# cell_adapter.net
KiCad netlist of a schematic drawn in Altium Designer
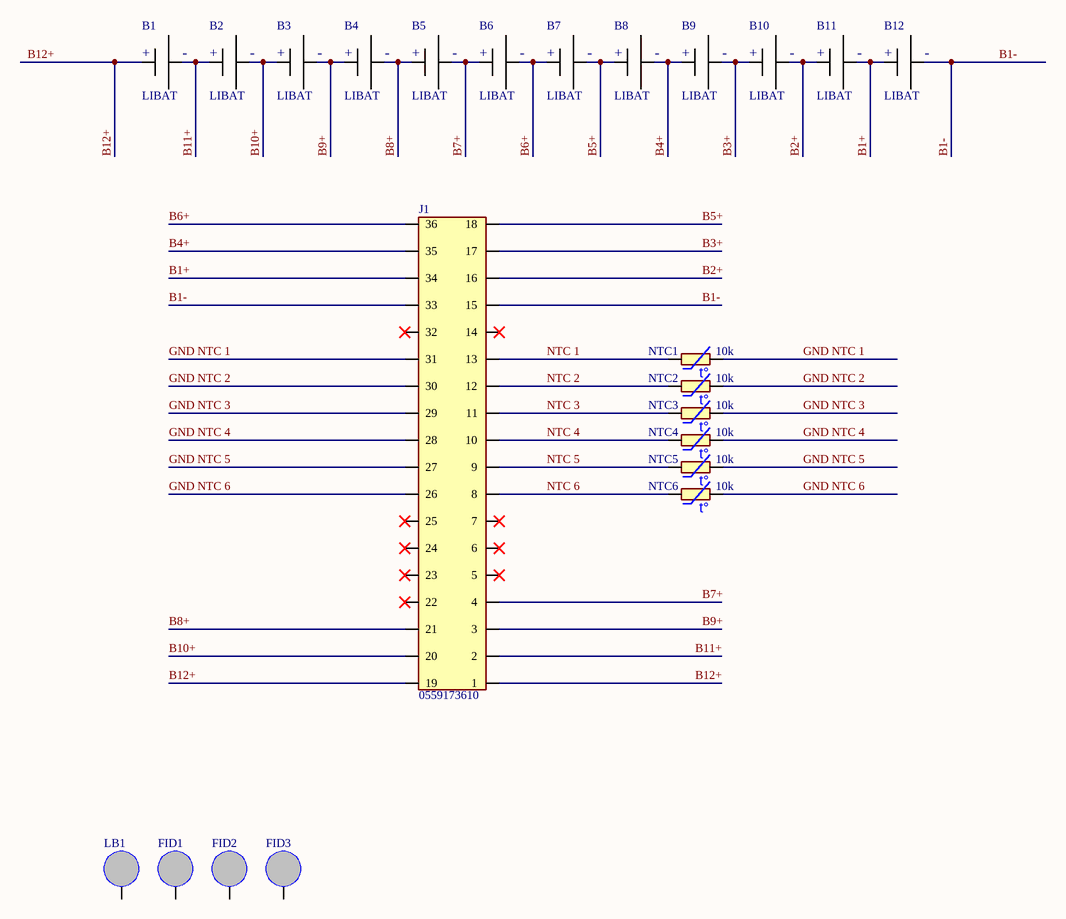
[diagram p0: cell_adapter.SchDoc]

(export (version "E")
  (design (tool "Eeschema 10.0.6"))
  (components
    (comp (ref "B1")
      (value "LIBAT")
      (footprint "Li-BATTERY")
      (libsource (lib "cell_adapter") (part "LI-BATTERY"))
    )
    (comp (ref "B2")
      (value "LIBAT")
      (footprint "Li-BATTERY")
      (libsource (lib "cell_adapter") (part "LI-BATTERY"))
    )
    (comp (ref "B3")
      (value "LIBAT")
      (footprint "Li-BATTERY")
      (libsource (lib "cell_adapter") (part "LI-BATTERY"))
    )
    (comp (ref "B4")
      (value "LIBAT")
      (footprint "Li-BATTERY")
      (libsource (lib "cell_adapter") (part "LI-BATTERY"))
    )
    (comp (ref "B5")
      (value "LIBAT")
      (footprint "Li-BATTERY")
      (libsource (lib "cell_adapter") (part "LI-BATTERY"))
    )
    (comp (ref "B6")
      (value "LIBAT")
      (footprint "Li-BATTERY")
      (libsource (lib "cell_adapter") (part "LI-BATTERY"))
    )
    (comp (ref "B7")
      (value "LIBAT")
      (footprint "Li-BATTERY")
      (libsource (lib "cell_adapter") (part "LI-BATTERY"))
    )
    (comp (ref "B8")
      (value "LIBAT")
      (footprint "Li-BATTERY")
      (libsource (lib "cell_adapter") (part "LI-BATTERY"))
    )
    (comp (ref "B9")
      (value "LIBAT")
      (footprint "Li-BATTERY")
      (libsource (lib "cell_adapter") (part "LI-BATTERY"))
    )
    (comp (ref "B10")
      (value "LIBAT")
      (footprint "Li-BATTERY")
      (libsource (lib "cell_adapter") (part "LI-BATTERY"))
    )
    (comp (ref "B11")
      (value "LIBAT")
      (footprint "Li-BATTERY")
      (libsource (lib "cell_adapter") (part "LI-BATTERY"))
    )
    (comp (ref "B12")
      (value "LIBAT")
      (footprint "Li-BATTERY")
      (libsource (lib "cell_adapter") (part "LI-BATTERY"))
    )
    (comp (ref "FID1")
      (value "PE PAD")
      (footprint "FIDUCIAL")
      (description "FIDUCIAL")
      (libsource (lib "cell_adapter") (part "PE PAD"))
    )
    (comp (ref "FID2")
      (value "PE PAD")
      (footprint "FIDUCIAL")
      (description "FIDUCIAL")
      (libsource (lib "cell_adapter") (part "PE PAD"))
    )
    (comp (ref "FID3")
      (value "PE PAD")
      (footprint "FIDUCIAL")
      (description "FIDUCIAL")
      (libsource (lib "cell_adapter") (part "PE PAD"))
    )
    (comp (ref "J1")
      (value "0559173610")
      (footprint "MICROFIT 36 VER")
      (description "CONN HEADER VERT 36POS 2MM")
      (libsource (lib "cell_adapter") (part "Header 18X2"))
    )
    (comp (ref "LB1")
      (value "PE PAD")
      (footprint "FIDUCIAL")
      (description "FIDUCIAL")
      (libsource (lib "cell_adapter") (part "PE PAD"))
    )
    (comp (ref "NTC1")
      (value "10k")
      (footprint "NTC0805-HC")
      (description "THERMISTOR NTC 10KOHM 3430K 0805")
      (fields
        (field (name "MANUFACTURER_PART_NUMBER") "NTCS0805E3103FLT")
        (field (name "MOUSER PART NUMBER") "594-NTCS0805E3103FLT")
      )
      (libsource (lib "cell_adapter") (part "NTCS0805E3103FLT"))
    )
    (comp (ref "NTC2")
      (value "10k")
      (footprint "NTC0805-HC")
      (description "THERMISTOR NTC 10KOHM 3430K 0805")
      (fields
        (field (name "MANUFACTURER_PART_NUMBER") "NTCS0805E3103FLT")
        (field (name "MOUSER PART NUMBER") "594-NTCS0805E3103FLT")
      )
      (libsource (lib "cell_adapter") (part "NTCS0805E3103FLT"))
    )
    (comp (ref "NTC3")
      (value "10k")
      (footprint "NTC0805-HC")
      (description "THERMISTOR NTC 10KOHM 3430K 0805")
      (fields
        (field (name "MANUFACTURER_PART_NUMBER") "NTCS0805E3103FLT")
        (field (name "MOUSER PART NUMBER") "594-NTCS0805E3103FLT")
      )
      (libsource (lib "cell_adapter") (part "NTCS0805E3103FLT"))
    )
    (comp (ref "NTC4")
      (value "10k")
      (footprint "NTC0805-HC")
      (description "THERMISTOR NTC 10KOHM 3430K 0805")
      (fields
        (field (name "MANUFACTURER_PART_NUMBER") "NTCS0805E3103FLT")
        (field (name "MOUSER PART NUMBER") "594-NTCS0805E3103FLT")
      )
      (libsource (lib "cell_adapter") (part "NTCS0805E3103FLT"))
    )
    (comp (ref "NTC5")
      (value "10k")
      (footprint "NTC0805-HC")
      (description "THERMISTOR NTC 10KOHM 3430K 0805")
      (fields
        (field (name "MANUFACTURER_PART_NUMBER") "NTCS0805E3103FLT")
        (field (name "MOUSER PART NUMBER") "594-NTCS0805E3103FLT")
      )
      (libsource (lib "cell_adapter") (part "NTCS0805E3103FLT"))
    )
    (comp (ref "NTC6")
      (value "10k")
      (footprint "NTC0805-HC")
      (description "THERMISTOR NTC 10KOHM 3430K 0805")
      (fields
        (field (name "MANUFACTURER_PART_NUMBER") "NTCS0805E3103FLT")
        (field (name "MOUSER PART NUMBER") "594-NTCS0805E3103FLT")
      )
      (libsource (lib "cell_adapter") (part "NTCS0805E3103FLT"))
    )
  )
  (nets
    (net (code "1") (name "/B1+") (class "Default")
      (node (ref "B11") (pin "2") (pinfunction "2_2") (pintype "passive"))
      (node (ref "B12") (pin "1") (pinfunction "1_1") (pintype "passive"))
      (node (ref "J1") (pin "34") (pinfunction "34_34") (pintype "passive"))
    )
    (net (code "2") (name "/B1-") (class "Default")
      (node (ref "B12") (pin "2") (pinfunction "2_2") (pintype "passive"))
      (node (ref "J1") (pin "15") (pinfunction "15_15") (pintype "passive"))
      (node (ref "J1") (pin "33") (pinfunction "33_33") (pintype "passive"))
    )
    (net (code "3") (name "/B2+") (class "Default")
      (node (ref "B10") (pin "2") (pinfunction "2_2") (pintype "passive"))
      (node (ref "B11") (pin "1") (pinfunction "1_1") (pintype "passive"))
      (node (ref "J1") (pin "16") (pinfunction "16_16") (pintype "passive"))
    )
    (net (code "4") (name "/B3+") (class "Default")
      (node (ref "B10") (pin "1") (pinfunction "1_1") (pintype "passive"))
      (node (ref "B9") (pin "2") (pinfunction "2_2") (pintype "passive"))
      (node (ref "J1") (pin "17") (pinfunction "17_17") (pintype "passive"))
    )
    (net (code "5") (name "/B4+") (class "Default")
      (node (ref "B8") (pin "2") (pinfunction "2_2") (pintype "passive"))
      (node (ref "B9") (pin "1") (pinfunction "1_1") (pintype "passive"))
      (node (ref "J1") (pin "35") (pinfunction "35_35") (pintype "passive"))
    )
    (net (code "6") (name "/B5+") (class "Default")
      (node (ref "B7") (pin "2") (pinfunction "2_2") (pintype "passive"))
      (node (ref "B8") (pin "1") (pinfunction "1_1") (pintype "passive"))
      (node (ref "J1") (pin "18") (pinfunction "18_18") (pintype "passive"))
    )
    (net (code "7") (name "/B6+") (class "Default")
      (node (ref "B6") (pin "2") (pinfunction "2_2") (pintype "passive"))
      (node (ref "B7") (pin "1") (pinfunction "1_1") (pintype "passive"))
      (node (ref "J1") (pin "36") (pinfunction "36_36") (pintype "passive"))
    )
    (net (code "8") (name "/B7+") (class "Default")
      (node (ref "B5") (pin "2") (pinfunction "2_2") (pintype "passive"))
      (node (ref "B6") (pin "1") (pinfunction "1_1") (pintype "passive"))
      (node (ref "J1") (pin "4") (pinfunction "4_4") (pintype "passive"))
    )
    (net (code "9") (name "/B8+") (class "Default")
      (node (ref "B4") (pin "2") (pinfunction "2_2") (pintype "passive"))
      (node (ref "B5") (pin "1") (pinfunction "1_1") (pintype "passive"))
      (node (ref "J1") (pin "21") (pinfunction "21_21") (pintype "passive"))
    )
    (net (code "10") (name "/B9+") (class "Default")
      (node (ref "B3") (pin "2") (pinfunction "2_2") (pintype "passive"))
      (node (ref "B4") (pin "1") (pinfunction "1_1") (pintype "passive"))
      (node (ref "J1") (pin "3") (pinfunction "3_3") (pintype "passive"))
    )
    (net (code "11") (name "/B10+") (class "Default")
      (node (ref "B2") (pin "2") (pinfunction "2_2") (pintype "passive"))
      (node (ref "B3") (pin "1") (pinfunction "1_1") (pintype "passive"))
      (node (ref "J1") (pin "20") (pinfunction "20_20") (pintype "passive"))
    )
    (net (code "12") (name "/B11+") (class "Default")
      (node (ref "B1") (pin "2") (pinfunction "2_2") (pintype "passive"))
      (node (ref "B2") (pin "1") (pinfunction "1_1") (pintype "passive"))
      (node (ref "J1") (pin "2") (pinfunction "2_2") (pintype "passive"))
    )
    (net (code "13") (name "/B12+") (class "Default")
      (node (ref "B1") (pin "1") (pinfunction "1_1") (pintype "passive"))
      (node (ref "J1") (pin "1") (pinfunction "1_1") (pintype "passive"))
      (node (ref "J1") (pin "19") (pinfunction "19_19") (pintype "passive"))
    )
    (net (code "14") (name "/GND NTC 1") (class "Default")
      (node (ref "J1") (pin "31") (pinfunction "31_31") (pintype "passive"))
      (node (ref "NTC1") (pin "2") (pinfunction "2_2") (pintype "passive"))
    )
    (net (code "15") (name "/GND NTC 2") (class "Default")
      (node (ref "J1") (pin "30") (pinfunction "30_30") (pintype "passive"))
      (node (ref "NTC2") (pin "2") (pinfunction "2_2") (pintype "passive"))
    )
    (net (code "16") (name "/GND NTC 3") (class "Default")
      (node (ref "J1") (pin "29") (pinfunction "29_29") (pintype "passive"))
      (node (ref "NTC3") (pin "2") (pinfunction "2_2") (pintype "passive"))
    )
    (net (code "17") (name "/GND NTC 4") (class "Default")
      (node (ref "J1") (pin "28") (pinfunction "28_28") (pintype "passive"))
      (node (ref "NTC4") (pin "2") (pinfunction "2_2") (pintype "passive"))
    )
    (net (code "18") (name "/GND NTC 5") (class "Default")
      (node (ref "J1") (pin "27") (pinfunction "27_27") (pintype "passive"))
      (node (ref "NTC5") (pin "2") (pinfunction "2_2") (pintype "passive"))
    )
    (net (code "19") (name "/GND NTC 6") (class "Default")
      (node (ref "J1") (pin "26") (pinfunction "26_26") (pintype "passive"))
      (node (ref "NTC6") (pin "2") (pinfunction "2_2") (pintype "passive"))
    )
    (net (code "20") (name "/NTC 1") (class "Default")
      (node (ref "J1") (pin "13") (pinfunction "13_13") (pintype "passive"))
      (node (ref "NTC1") (pin "1") (pinfunction "1_1") (pintype "passive"))
    )
    (net (code "21") (name "/NTC 2") (class "Default")
      (node (ref "J1") (pin "12") (pinfunction "12_12") (pintype "passive"))
      (node (ref "NTC2") (pin "1") (pinfunction "1_1") (pintype "passive"))
    )
    (net (code "22") (name "/NTC 3") (class "Default")
      (node (ref "J1") (pin "11") (pinfunction "11_11") (pintype "passive"))
      (node (ref "NTC3") (pin "1") (pinfunction "1_1") (pintype "passive"))
    )
    (net (code "23") (name "/NTC 4") (class "Default")
      (node (ref "J1") (pin "10") (pinfunction "10_10") (pintype "passive"))
      (node (ref "NTC4") (pin "1") (pinfunction "1_1") (pintype "passive"))
    )
    (net (code "24") (name "/NTC 5") (class "Default")
      (node (ref "J1") (pin "9") (pinfunction "9_9") (pintype "passive"))
      (node (ref "NTC5") (pin "1") (pinfunction "1_1") (pintype "passive"))
    )
    (net (code "25") (name "/NTC 6") (class "Default")
      (node (ref "J1") (pin "8") (pinfunction "8_8") (pintype "passive"))
      (node (ref "NTC6") (pin "1") (pinfunction "1_1") (pintype "passive"))
    )
    (net (code "26") (name "unconnected-(FID1-Pad1)") (class "Default")
      (node (ref "FID1") (pin "1") (pinfunction "1_1") (pintype "passive"))
    )
    (net (code "27") (name "unconnected-(FID2-Pad1)") (class "Default")
      (node (ref "FID2") (pin "1") (pinfunction "1_1") (pintype "passive"))
    )
    (net (code "28") (name "unconnected-(FID3-Pad1)") (class "Default")
      (node (ref "FID3") (pin "1") (pinfunction "1_1") (pintype "passive"))
    )
    (net (code "29") (name "unconnected-(J1-Pad5)") (class "Default")
      (node (ref "J1") (pin "5") (pinfunction "5_5") (pintype "passive+no_connect"))
    )
    (net (code "30") (name "unconnected-(J1-Pad6)") (class "Default")
      (node (ref "J1") (pin "6") (pinfunction "6_6") (pintype "passive+no_connect"))
    )
    (net (code "31") (name "unconnected-(J1-Pad7)") (class "Default")
      (node (ref "J1") (pin "7") (pinfunction "7_7") (pintype "passive+no_connect"))
    )
    (net (code "32") (name "unconnected-(J1-Pad14)") (class "Default")
      (node (ref "J1") (pin "14") (pinfunction "14_14") (pintype "passive+no_connect"))
    )
    (net (code "33") (name "unconnected-(J1-Pad22)") (class "Default")
      (node (ref "J1") (pin "22") (pinfunction "22_22") (pintype "passive+no_connect"))
    )
    (net (code "34") (name "unconnected-(J1-Pad23)") (class "Default")
      (node (ref "J1") (pin "23") (pinfunction "23_23") (pintype "passive+no_connect"))
    )
    (net (code "35") (name "unconnected-(J1-Pad24)") (class "Default")
      (node (ref "J1") (pin "24") (pinfunction "24_24") (pintype "passive+no_connect"))
    )
    (net (code "36") (name "unconnected-(J1-Pad25)") (class "Default")
      (node (ref "J1") (pin "25") (pinfunction "25_25") (pintype "passive+no_connect"))
    )
    (net (code "37") (name "unconnected-(J1-Pad32)") (class "Default")
      (node (ref "J1") (pin "32") (pinfunction "32_32") (pintype "passive+no_connect"))
    )
    (net (code "38") (name "unconnected-(LB1-Pad1)") (class "Default")
      (node (ref "LB1") (pin "1") (pinfunction "1_1") (pintype "passive"))
    )
  )
)
